# POTENCIOSTATO_22-11-2018.net
KiCad netlist of a schematic drawn in EAGLE
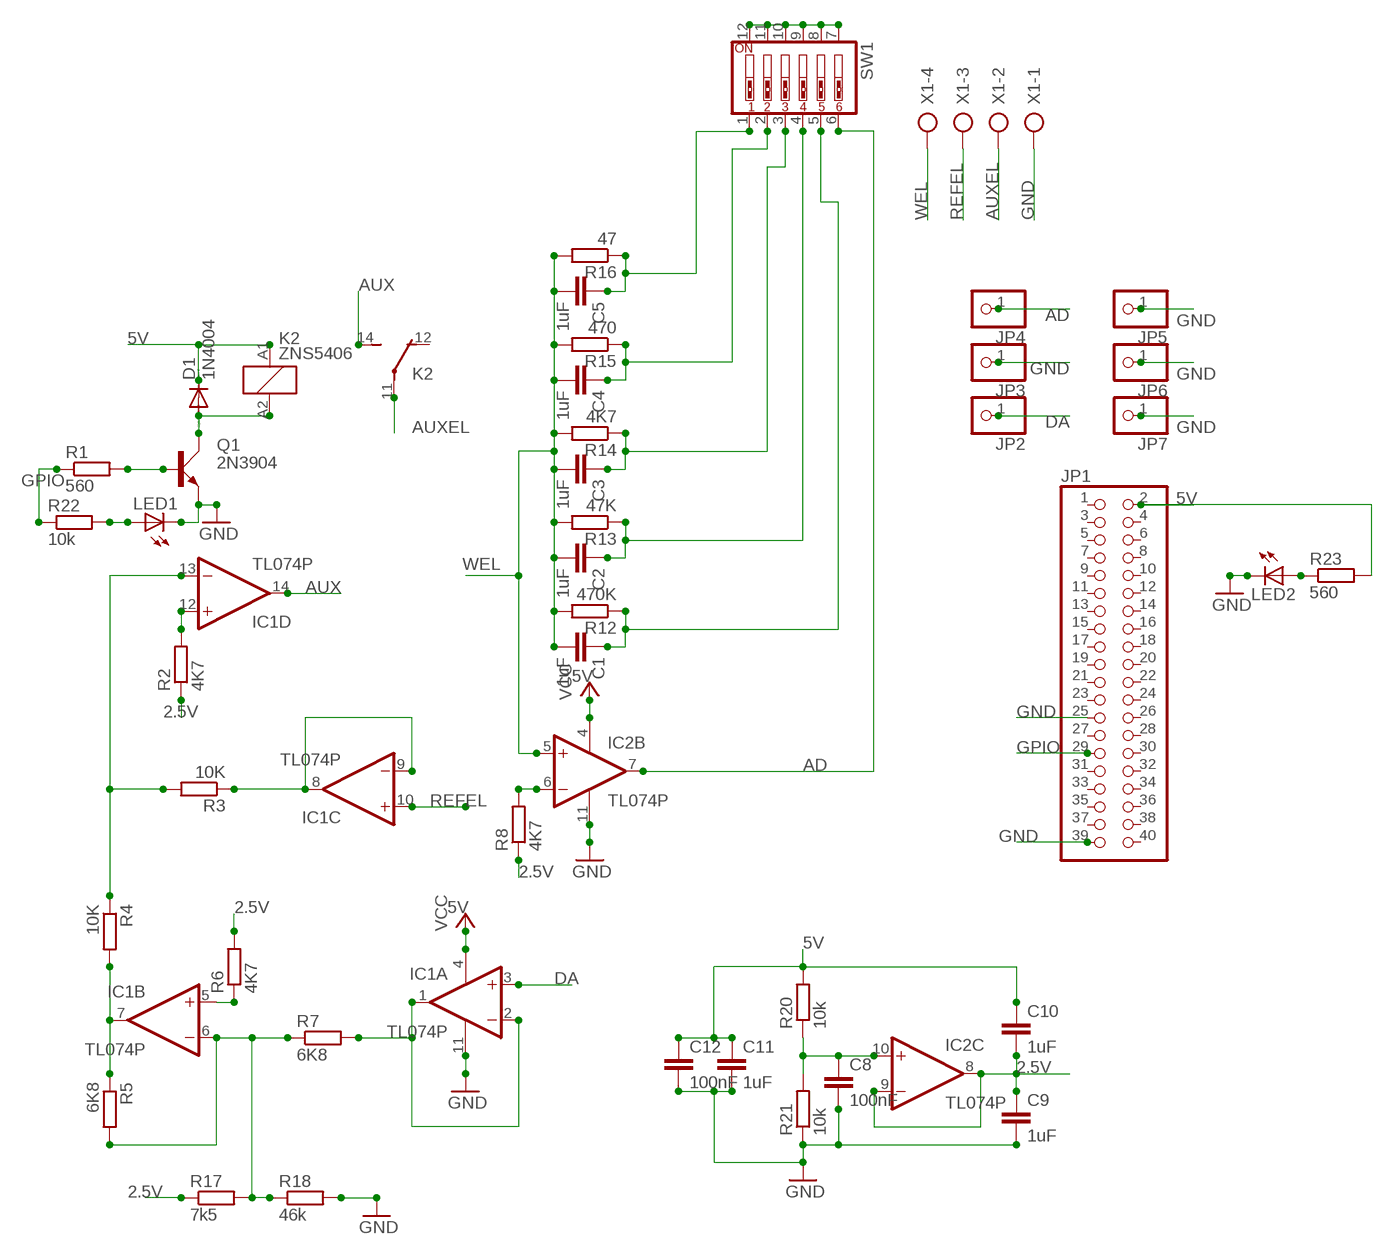
[diagram p0: schematic, sheet 1]

(export (version "E")
  (design (tool "Eeschema 10.0.6"))
  (components
    (comp (ref "C1")
      (value "1uF")
      (footprint "eagle-import:C0805")
      (libsource (lib "eagle-import") (part "C-EUC0805"))
    )
    (comp (ref "C2")
      (value "1uF")
      (footprint "eagle-import:C0805")
      (libsource (lib "eagle-import") (part "C-EUC0805"))
    )
    (comp (ref "C3")
      (value "1uF")
      (footprint "eagle-import:C0805")
      (libsource (lib "eagle-import") (part "C-EUC0805"))
    )
    (comp (ref "C4")
      (value "1uF")
      (footprint "eagle-import:C0805")
      (libsource (lib "eagle-import") (part "C-EUC0805"))
    )
    (comp (ref "C5")
      (value "1uF")
      (footprint "eagle-import:C0805")
      (libsource (lib "eagle-import") (part "C-EUC0805"))
    )
    (comp (ref "C8")
      (value "100nF")
      (footprint "eagle-import:C0805")
      (libsource (lib "eagle-import") (part "C-EUC0805"))
    )
    (comp (ref "C9")
      (value "1uF")
      (footprint "eagle-import:C0805")
      (libsource (lib "eagle-import") (part "C-EUC0805"))
    )
    (comp (ref "C10")
      (value "1uF")
      (footprint "eagle-import:C0805")
      (libsource (lib "eagle-import") (part "C-EUC0805"))
    )
    (comp (ref "C11")
      (value "1uF")
      (footprint "eagle-import:C0805")
      (libsource (lib "eagle-import") (part "C-EUC0805"))
    )
    (comp (ref "C12")
      (value "100nF")
      (footprint "eagle-import:C0805")
      (libsource (lib "eagle-import") (part "C-EUC0805"))
    )
    (comp (ref "D1")
      (value "1N4004")
      (footprint "eagle-import:DO41-10")
      (libsource (lib "eagle-import") (part "1N4004"))
    )
    (comp (ref "IC1")
      (value "TL074P")
      (footprint "eagle-import:DIL14")
      (libsource (lib "eagle-import") (part "TL074P"))
    )
    (comp (ref "IC2")
      (value "TL074P")
      (footprint "eagle-import:DIL14")
      (libsource (lib "eagle-import") (part "TL074P"))
    )
    (comp (ref "JP1")
      (value "PINHD-2X20/90")
      (footprint "eagle-import:2X20_90")
      (libsource (lib "eagle-import") (part "PINHD-2X20/90"))
    )
    (comp (ref "JP2")
      (value "PINHD-1X1")
      (footprint "eagle-import:1X01")
      (libsource (lib "eagle-import") (part "PINHD-1X1"))
    )
    (comp (ref "JP3")
      (value "PINHD-1X1")
      (footprint "eagle-import:1X01")
      (libsource (lib "eagle-import") (part "PINHD-1X1"))
    )
    (comp (ref "JP4")
      (value "PINHD-1X1")
      (footprint "eagle-import:1X01")
      (libsource (lib "eagle-import") (part "PINHD-1X1"))
    )
    (comp (ref "JP5")
      (value "PINHD-1X1")
      (footprint "eagle-import:1X01")
      (libsource (lib "eagle-import") (part "PINHD-1X1"))
    )
    (comp (ref "JP6")
      (value "PINHD-1X1")
      (footprint "eagle-import:1X01")
      (libsource (lib "eagle-import") (part "PINHD-1X1"))
    )
    (comp (ref "JP7")
      (value "PINHD-1X1")
      (footprint "eagle-import:1X01")
      (libsource (lib "eagle-import") (part "PINHD-1X1"))
    )
    (comp (ref "K2")
      (value "ZNS5406")
      (footprint "eagle-import:ZN5")
      (libsource (lib "eagle-import") (part "ZNS5406"))
    )
    (comp (ref "LED1")
      (value "LEDSML0805")
      (footprint "eagle-import:SML0805")
      (libsource (lib "eagle-import") (part "LEDSML0805"))
    )
    (comp (ref "LED2")
      (value "LEDSML0805")
      (footprint "eagle-import:SML0805")
      (libsource (lib "eagle-import") (part "LEDSML0805"))
    )
    (comp (ref "Q1")
      (value "2N3904")
      (footprint "eagle-import:TO92D")
      (libsource (lib "eagle-import") (part "2N3904"))
    )
    (comp (ref "R1")
      (value "560")
      (footprint "eagle-import:R0805")
      (libsource (lib "eagle-import") (part "R-EU_R0805"))
    )
    (comp (ref "R2")
      (value "4K7")
      (footprint "eagle-import:R0805")
      (libsource (lib "eagle-import") (part "R-EU_R0805"))
    )
    (comp (ref "R3")
      (value "10K")
      (footprint "eagle-import:R0805")
      (libsource (lib "eagle-import") (part "R-EU_R0805"))
    )
    (comp (ref "R4")
      (value "10K")
      (footprint "eagle-import:R0805")
      (libsource (lib "eagle-import") (part "R-EU_R0805"))
    )
    (comp (ref "R5")
      (value "6K8")
      (footprint "eagle-import:R0805")
      (libsource (lib "eagle-import") (part "R-EU_R0805"))
    )
    (comp (ref "R6")
      (value "4K7")
      (footprint "eagle-import:R0805")
      (libsource (lib "eagle-import") (part "R-EU_R0805"))
    )
    (comp (ref "R7")
      (value "6K8")
      (footprint "eagle-import:R0805")
      (libsource (lib "eagle-import") (part "R-EU_R0805"))
    )
    (comp (ref "R8")
      (value "4K7")
      (footprint "eagle-import:R0805")
      (libsource (lib "eagle-import") (part "R-EU_R0805"))
    )
    (comp (ref "R12")
      (value "470K")
      (footprint "eagle-import:R0805")
      (libsource (lib "eagle-import") (part "R-EU_R0805"))
    )
    (comp (ref "R13")
      (value "47K")
      (footprint "eagle-import:R0805")
      (libsource (lib "eagle-import") (part "R-EU_R0805"))
    )
    (comp (ref "R14")
      (value "4K7")
      (footprint "eagle-import:R0805")
      (libsource (lib "eagle-import") (part "R-EU_R0805"))
    )
    (comp (ref "R15")
      (value "470")
      (footprint "eagle-import:R0805")
      (libsource (lib "eagle-import") (part "R-EU_R0805"))
    )
    (comp (ref "R16")
      (value "47")
      (footprint "eagle-import:R0805")
      (libsource (lib "eagle-import") (part "R-EU_R0805"))
    )
    (comp (ref "R17")
      (value "7k5")
      (footprint "eagle-import:R0805")
      (libsource (lib "eagle-import") (part "R-EU_R0805"))
    )
    (comp (ref "R18")
      (value "46k")
      (footprint "eagle-import:R0805")
      (libsource (lib "eagle-import") (part "R-EU_R0805"))
    )
    (comp (ref "R20")
      (value "10k")
      (footprint "eagle-import:R0805")
      (libsource (lib "eagle-import") (part "R-EU_R0805"))
    )
    (comp (ref "R21")
      (value "10k")
      (footprint "eagle-import:R0805")
      (libsource (lib "eagle-import") (part "R-EU_R0805"))
    )
    (comp (ref "R22")
      (value "10k")
      (footprint "eagle-import:R0805")
      (libsource (lib "eagle-import") (part "R-EU_R0805"))
    )
    (comp (ref "R23")
      (value "560")
      (footprint "eagle-import:R0805")
      (libsource (lib "eagle-import") (part "R-EU_R0805"))
    )
    (comp (ref "SW1")
      (value "SW_DIP-6")
      (footprint "eagle-import:EDG-06")
      (libsource (lib "eagle-import") (part "SW_DIP-6"))
    )
    (comp (ref "X1")
      (value "AK500/4")
      (footprint "eagle-import:AK500_4")
      (libsource (lib "eagle-import") (part "AK500/4"))
    )
  )
  (nets
    (net (code "1") (name "/2.5V") (class "Default")
      (node (ref "C10") (pin "2") (pinfunction "2_2") (pintype "passive"))
      (node (ref "C9") (pin "1") (pinfunction "1_1") (pintype "passive"))
      (node (ref "IC2") (pin "8") (pinfunction "OUT_8") (pintype "output"))
      (node (ref "IC2") (pin "9") (pinfunction "-IN_9") (pintype "input"))
      (node (ref "R17") (pin "1") (pinfunction "1_1") (pintype "passive"))
      (node (ref "R2") (pin "1") (pinfunction "1_1") (pintype "passive"))
      (node (ref "R6") (pin "2") (pinfunction "2_2") (pintype "passive"))
      (node (ref "R8") (pin "1") (pinfunction "1_1") (pintype "passive"))
    )
    (net (code "2") (name "/AD") (class "Default")
      (node (ref "IC2") (pin "7") (pinfunction "OUT_7") (pintype "output"))
      (node (ref "JP4") (pin "1") (pinfunction "1_1") (pintype "passive"))
      (node (ref "SW1") (pin "6") (pinfunction "6_6") (pintype "passive"))
    )
    (net (code "3") (name "/AUX") (class "Default")
      (node (ref "IC1") (pin "14") (pinfunction "OUT_14") (pintype "output"))
      (node (ref "K2") (pin "14") (pinfunction "S_14") (pintype "passive"))
    )
    (net (code "4") (name "/AUXEL") (class "Default")
      (node (ref "K2") (pin "11") (pinfunction "P_11") (pintype "passive"))
      (node (ref "X1") (pin "2") (pinfunction "KL_2") (pintype "passive"))
    )
    (net (code "5") (name "/DA") (class "Default")
      (node (ref "IC1") (pin "3") (pinfunction "+IN_3") (pintype "input"))
      (node (ref "JP2") (pin "1") (pinfunction "1_1") (pintype "passive"))
    )
    (net (code "6") (name "/GPIO") (class "Default")
      (node (ref "JP1") (pin "29") (pinfunction "29_29") (pintype "passive"))
      (node (ref "R1") (pin "1") (pinfunction "1_1") (pintype "passive"))
      (node (ref "R22") (pin "1") (pinfunction "1_1") (pintype "passive"))
    )
    (net (code "7") (name "/REFEL") (class "Default")
      (node (ref "IC1") (pin "10") (pinfunction "+IN_10") (pintype "input"))
      (node (ref "X1") (pin "3") (pinfunction "KL_3") (pintype "passive"))
    )
    (net (code "8") (name "/WEL") (class "Default")
      (node (ref "C1") (pin "2") (pinfunction "2_2") (pintype "passive"))
      (node (ref "C2") (pin "2") (pinfunction "2_2") (pintype "passive"))
      (node (ref "C3") (pin "2") (pinfunction "2_2") (pintype "passive"))
      (node (ref "C4") (pin "2") (pinfunction "2_2") (pintype "passive"))
      (node (ref "C5") (pin "2") (pinfunction "2_2") (pintype "passive"))
      (node (ref "IC2") (pin "5") (pinfunction "+IN_5") (pintype "input"))
      (node (ref "R12") (pin "2") (pinfunction "2_2") (pintype "passive"))
      (node (ref "R13") (pin "2") (pinfunction "2_2") (pintype "passive"))
      (node (ref "R14") (pin "2") (pinfunction "2_2") (pintype "passive"))
      (node (ref "R15") (pin "2") (pinfunction "2_2") (pintype "passive"))
      (node (ref "R16") (pin "2") (pinfunction "2_2") (pintype "passive"))
      (node (ref "X1") (pin "4") (pinfunction "KL_4") (pintype "passive"))
    )
    (net (code "9") (name "GND") (class "Default")
      (node (ref "C11") (pin "2") (pinfunction "2_2") (pintype "passive"))
      (node (ref "C12") (pin "2") (pinfunction "2_2") (pintype "passive"))
      (node (ref "C8") (pin "2") (pinfunction "2_2") (pintype "passive"))
      (node (ref "C9") (pin "2") (pinfunction "2_2") (pintype "passive"))
      (node (ref "IC1") (pin "11") (pinfunction "V-_11") (pintype "power_in"))
      (node (ref "IC2") (pin "11") (pinfunction "V-_11") (pintype "power_in"))
      (node (ref "JP1") (pin "25") (pinfunction "25_25") (pintype "passive"))
      (node (ref "JP1") (pin "39") (pinfunction "39_39") (pintype "passive"))
      (node (ref "JP3") (pin "1") (pinfunction "1_1") (pintype "passive"))
      (node (ref "JP5") (pin "1") (pinfunction "1_1") (pintype "passive"))
      (node (ref "JP6") (pin "1") (pinfunction "1_1") (pintype "passive"))
      (node (ref "JP7") (pin "1") (pinfunction "1_1") (pintype "passive"))
      (node (ref "LED1") (pin "C") (pinfunction "C_C") (pintype "passive"))
      (node (ref "LED2") (pin "C") (pinfunction "C_C") (pintype "passive"))
      (node (ref "Q1") (pin "E") (pinfunction "E_E") (pintype "passive"))
      (node (ref "R18") (pin "2") (pinfunction "2_2") (pintype "passive"))
      (node (ref "R21") (pin "1") (pinfunction "1_1") (pintype "passive"))
      (node (ref "X1") (pin "1") (pinfunction "KL_1") (pintype "passive"))
    )
    (net (code "10") (name "Net-(C1-Pad1)") (class "Default")
      (node (ref "C1") (pin "1") (pinfunction "1_1") (pintype "passive"))
      (node (ref "R12") (pin "1") (pinfunction "1_1") (pintype "passive"))
      (node (ref "SW1") (pin "5") (pinfunction "5_5") (pintype "passive"))
    )
    (net (code "11") (name "Net-(C2-Pad1)") (class "Default")
      (node (ref "C2") (pin "1") (pinfunction "1_1") (pintype "passive"))
      (node (ref "R13") (pin "1") (pinfunction "1_1") (pintype "passive"))
      (node (ref "SW1") (pin "4") (pinfunction "4_4") (pintype "passive"))
    )
    (net (code "12") (name "Net-(C3-Pad1)") (class "Default")
      (node (ref "C3") (pin "1") (pinfunction "1_1") (pintype "passive"))
      (node (ref "R14") (pin "1") (pinfunction "1_1") (pintype "passive"))
      (node (ref "SW1") (pin "3") (pinfunction "3_3") (pintype "passive"))
    )
    (net (code "13") (name "Net-(C4-Pad1)") (class "Default")
      (node (ref "C4") (pin "1") (pinfunction "1_1") (pintype "passive"))
      (node (ref "R15") (pin "1") (pinfunction "1_1") (pintype "passive"))
      (node (ref "SW1") (pin "2") (pinfunction "2_2") (pintype "passive"))
    )
    (net (code "14") (name "Net-(C5-Pad1)") (class "Default")
      (node (ref "C5") (pin "1") (pinfunction "1_1") (pintype "passive"))
      (node (ref "R16") (pin "1") (pinfunction "1_1") (pintype "passive"))
      (node (ref "SW1") (pin "1") (pinfunction "1_1") (pintype "passive"))
    )
    (net (code "15") (name "Net-(IC1A--IN)") (class "Default")
      (node (ref "IC1") (pin "1") (pinfunction "OUT_1") (pintype "output"))
      (node (ref "IC1") (pin "2") (pinfunction "-IN_2") (pintype "input"))
      (node (ref "R7") (pin "2") (pinfunction "2_2") (pintype "passive"))
    )
    (net (code "16") (name "Net-(IC1B-+IN)") (class "Default")
      (node (ref "IC1") (pin "5") (pinfunction "+IN_5") (pintype "input"))
      (node (ref "R6") (pin "1") (pinfunction "1_1") (pintype "passive"))
    )
    (net (code "17") (name "Net-(IC1B--IN)") (class "Default")
      (node (ref "IC1") (pin "6") (pinfunction "-IN_6") (pintype "input"))
      (node (ref "R17") (pin "2") (pinfunction "2_2") (pintype "passive"))
      (node (ref "R18") (pin "1") (pinfunction "1_1") (pintype "passive"))
      (node (ref "R5") (pin "2") (pinfunction "2_2") (pintype "passive"))
      (node (ref "R7") (pin "1") (pinfunction "1_1") (pintype "passive"))
    )
    (net (code "18") (name "Net-(IC1B-OUT)") (class "Default")
      (node (ref "IC1") (pin "7") (pinfunction "OUT_7") (pintype "output"))
      (node (ref "R4") (pin "2") (pinfunction "2_2") (pintype "passive"))
      (node (ref "R5") (pin "1") (pinfunction "1_1") (pintype "passive"))
    )
    (net (code "19") (name "Net-(IC1C--IN)") (class "Default")
      (node (ref "IC1") (pin "8") (pinfunction "OUT_8") (pintype "output"))
      (node (ref "IC1") (pin "9") (pinfunction "-IN_9") (pintype "input"))
      (node (ref "R3") (pin "1") (pinfunction "1_1") (pintype "passive"))
    )
    (net (code "20") (name "Net-(IC1D-+IN)") (class "Default")
      (node (ref "IC1") (pin "12") (pinfunction "+IN_12") (pintype "input"))
      (node (ref "R2") (pin "2") (pinfunction "2_2") (pintype "passive"))
    )
    (net (code "21") (name "Net-(IC1D--IN)") (class "Default")
      (node (ref "IC1") (pin "13") (pinfunction "-IN_13") (pintype "input"))
      (node (ref "R3") (pin "2") (pinfunction "2_2") (pintype "passive"))
      (node (ref "R4") (pin "1") (pinfunction "1_1") (pintype "passive"))
    )
    (net (code "22") (name "Net-(IC2B--IN)") (class "Default")
      (node (ref "IC2") (pin "6") (pinfunction "-IN_6") (pintype "input"))
      (node (ref "R8") (pin "2") (pinfunction "2_2") (pintype "passive"))
    )
    (net (code "23") (name "Net-(IC2C-+IN)") (class "Default")
      (node (ref "C8") (pin "1") (pinfunction "1_1") (pintype "passive"))
      (node (ref "IC2") (pin "10") (pinfunction "+IN_10") (pintype "input"))
      (node (ref "R20") (pin "1") (pinfunction "1_1") (pintype "passive"))
      (node (ref "R21") (pin "2") (pinfunction "2_2") (pintype "passive"))
    )
    (net (code "24") (name "Net-(K2A-2)") (class "Default")
      (node (ref "D1") (pin "A") (pinfunction "A_A") (pintype "passive"))
      (node (ref "K2") (pin "A2") (pinfunction "2_A2") (pintype "passive"))
      (node (ref "Q1") (pin "C") (pinfunction "C_C") (pintype "passive"))
    )
    (net (code "25") (name "Net-(LED1-PadA)") (class "Default")
      (node (ref "LED1") (pin "A") (pinfunction "A_A") (pintype "passive"))
      (node (ref "R22") (pin "2") (pinfunction "2_2") (pintype "passive"))
    )
    (net (code "26") (name "Net-(LED2-PadA)") (class "Default")
      (node (ref "LED2") (pin "A") (pinfunction "A_A") (pintype "passive"))
      (node (ref "R23") (pin "1") (pinfunction "1_1") (pintype "passive"))
    )
    (net (code "27") (name "Net-(Q1-PadB)") (class "Default")
      (node (ref "Q1") (pin "B") (pinfunction "B_B") (pintype "passive"))
      (node (ref "R1") (pin "2") (pinfunction "2_2") (pintype "passive"))
    )
    (net (code "28") (name "Net-(SW1-Pad10)") (class "Default")
      (node (ref "SW1") (pin "10") (pinfunction "10_10") (pintype "passive"))
      (node (ref "SW1") (pin "11") (pinfunction "11_11") (pintype "passive"))
      (node (ref "SW1") (pin "12") (pinfunction "12_12") (pintype "passive"))
      (node (ref "SW1") (pin "7") (pinfunction "7_7") (pintype "passive"))
      (node (ref "SW1") (pin "8") (pinfunction "8_8") (pintype "passive"))
      (node (ref "SW1") (pin "9") (pinfunction "9_9") (pintype "passive"))
    )
    (net (code "29") (name "VCC") (class "Default")
      (node (ref "C10") (pin "1") (pinfunction "1_1") (pintype "passive"))
      (node (ref "C11") (pin "1") (pinfunction "1_1") (pintype "passive"))
      (node (ref "C12") (pin "1") (pinfunction "1_1") (pintype "passive"))
      (node (ref "D1") (pin "C") (pinfunction "C_C") (pintype "passive"))
      (node (ref "IC1") (pin "4") (pinfunction "V+_4") (pintype "power_in"))
      (node (ref "IC2") (pin "4") (pinfunction "V+_4") (pintype "power_in"))
      (node (ref "JP1") (pin "2") (pinfunction "2_2") (pintype "passive"))
      (node (ref "K2") (pin "A1") (pinfunction "1_A1") (pintype "passive"))
      (node (ref "R20") (pin "2") (pinfunction "2_2") (pintype "passive"))
      (node (ref "R23") (pin "2") (pinfunction "2_2") (pintype "passive"))
    )
    (net (code "30") (name "unconnected-(JP1-Pad1)") (class "Default")
      (node (ref "JP1") (pin "1") (pinfunction "1_1") (pintype "passive"))
    )
    (net (code "31") (name "unconnected-(JP1-Pad3)") (class "Default")
      (node (ref "JP1") (pin "3") (pinfunction "3_3") (pintype "passive"))
    )
    (net (code "32") (name "unconnected-(JP1-Pad4)") (class "Default")
      (node (ref "JP1") (pin "4") (pinfunction "4_4") (pintype "passive"))
    )
    (net (code "33") (name "unconnected-(JP1-Pad5)") (class "Default")
      (node (ref "JP1") (pin "5") (pinfunction "5_5") (pintype "passive"))
    )
    (net (code "34") (name "unconnected-(JP1-Pad6)") (class "Default")
      (node (ref "JP1") (pin "6") (pinfunction "6_6") (pintype "passive"))
    )
    (net (code "35") (name "unconnected-(JP1-Pad7)") (class "Default")
      (node (ref "JP1") (pin "7") (pinfunction "7_7") (pintype "passive"))
    )
    (net (code "36") (name "unconnected-(JP1-Pad8)") (class "Default")
      (node (ref "JP1") (pin "8") (pinfunction "8_8") (pintype "passive"))
    )
    (net (code "37") (name "unconnected-(JP1-Pad9)") (class "Default")
      (node (ref "JP1") (pin "9") (pinfunction "9_9") (pintype "passive"))
    )
    (net (code "38") (name "unconnected-(JP1-Pad10)") (class "Default")
      (node (ref "JP1") (pin "10") (pinfunction "10_10") (pintype "passive"))
    )
    (net (code "39") (name "unconnected-(JP1-Pad11)") (class "Default")
      (node (ref "JP1") (pin "11") (pinfunction "11_11") (pintype "passive"))
    )
    (net (code "40") (name "unconnected-(JP1-Pad12)") (class "Default")
      (node (ref "JP1") (pin "12") (pinfunction "12_12") (pintype "passive"))
    )
    (net (code "41") (name "unconnected-(JP1-Pad13)") (class "Default")
      (node (ref "JP1") (pin "13") (pinfunction "13_13") (pintype "passive"))
    )
    (net (code "42") (name "unconnected-(JP1-Pad14)") (class "Default")
      (node (ref "JP1") (pin "14") (pinfunction "14_14") (pintype "passive"))
    )
    (net (code "43") (name "unconnected-(JP1-Pad15)") (class "Default")
      (node (ref "JP1") (pin "15") (pinfunction "15_15") (pintype "passive"))
    )
    (net (code "44") (name "unconnected-(JP1-Pad16)") (class "Default")
      (node (ref "JP1") (pin "16") (pinfunction "16_16") (pintype "passive"))
    )
    (net (code "45") (name "unconnected-(JP1-Pad17)") (class "Default")
      (node (ref "JP1") (pin "17") (pinfunction "17_17") (pintype "passive"))
    )
    (net (code "46") (name "unconnected-(JP1-Pad18)") (class "Default")
      (node (ref "JP1") (pin "18") (pinfunction "18_18") (pintype "passive"))
    )
    (net (code "47") (name "unconnected-(JP1-Pad19)") (class "Default")
      (node (ref "JP1") (pin "19") (pinfunction "19_19") (pintype "passive"))
    )
    (net (code "48") (name "unconnected-(JP1-Pad20)") (class "Default")
      (node (ref "JP1") (pin "20") (pinfunction "20_20") (pintype "passive"))
    )
    (net (code "49") (name "unconnected-(JP1-Pad21)") (class "Default")
      (node (ref "JP1") (pin "21") (pinfunction "21_21") (pintype "passive"))
    )
    (net (code "50") (name "unconnected-(JP1-Pad22)") (class "Default")
      (node (ref "JP1") (pin "22") (pinfunction "22_22") (pintype "passive"))
    )
    (net (code "51") (name "unconnected-(JP1-Pad23)") (class "Default")
      (node (ref "JP1") (pin "23") (pinfunction "23_23") (pintype "passive"))
    )
    (net (code "52") (name "unconnected-(JP1-Pad24)") (class "Default")
      (node (ref "JP1") (pin "24") (pinfunction "24_24") (pintype "passive"))
    )
    (net (code "53") (name "unconnected-(JP1-Pad26)") (class "Default")
      (node (ref "JP1") (pin "26") (pinfunction "26_26") (pintype "passive"))
    )
    (net (code "54") (name "unconnected-(JP1-Pad27)") (class "Default")
      (node (ref "JP1") (pin "27") (pinfunction "27_27") (pintype "passive"))
    )
    (net (code "55") (name "unconnected-(JP1-Pad28)") (class "Default")
      (node (ref "JP1") (pin "28") (pinfunction "28_28") (pintype "passive"))
    )
    (net (code "56") (name "unconnected-(JP1-Pad30)") (class "Default")
      (node (ref "JP1") (pin "30") (pinfunction "30_30") (pintype "passive"))
    )
    (net (code "57") (name "unconnected-(JP1-Pad31)") (class "Default")
      (node (ref "JP1") (pin "31") (pinfunction "31_31") (pintype "passive"))
    )
    (net (code "58") (name "unconnected-(JP1-Pad32)") (class "Default")
      (node (ref "JP1") (pin "32") (pinfunction "32_32") (pintype "passive"))
    )
    (net (code "59") (name "unconnected-(JP1-Pad33)") (class "Default")
      (node (ref "JP1") (pin "33") (pinfunction "33_33") (pintype "passive"))
    )
    (net (code "60") (name "unconnected-(JP1-Pad34)") (class "Default")
      (node (ref "JP1") (pin "34") (pinfunction "34_34") (pintype "passive"))
    )
    (net (code "61") (name "unconnected-(JP1-Pad35)") (class "Default")
      (node (ref "JP1") (pin "35") (pinfunction "35_35") (pintype "passive"))
    )
    (net (code "62") (name "unconnected-(JP1-Pad36)") (class "Default")
      (node (ref "JP1") (pin "36") (pinfunction "36_36") (pintype "passive"))
    )
    (net (code "63") (name "unconnected-(JP1-Pad37)") (class "Default")
      (node (ref "JP1") (pin "37") (pinfunction "37_37") (pintype "passive"))
    )
    (net (code "64") (name "unconnected-(JP1-Pad38)") (class "Default")
      (node (ref "JP1") (pin "38") (pinfunction "38_38") (pintype "passive"))
    )
    (net (code "65") (name "unconnected-(JP1-Pad40)") (class "Default")
      (node (ref "JP1") (pin "40") (pinfunction "40_40") (pintype "passive"))
    )
    (net (code "66") (name "unconnected-(K2B-O-Pad12)") (class "Default")
      (node (ref "K2") (pin "12") (pinfunction "O_12") (pintype "passive"))
    )
  )
)
